# AudioHacker_v1_2.net
KiCad netlist of a schematic drawn in EAGLE
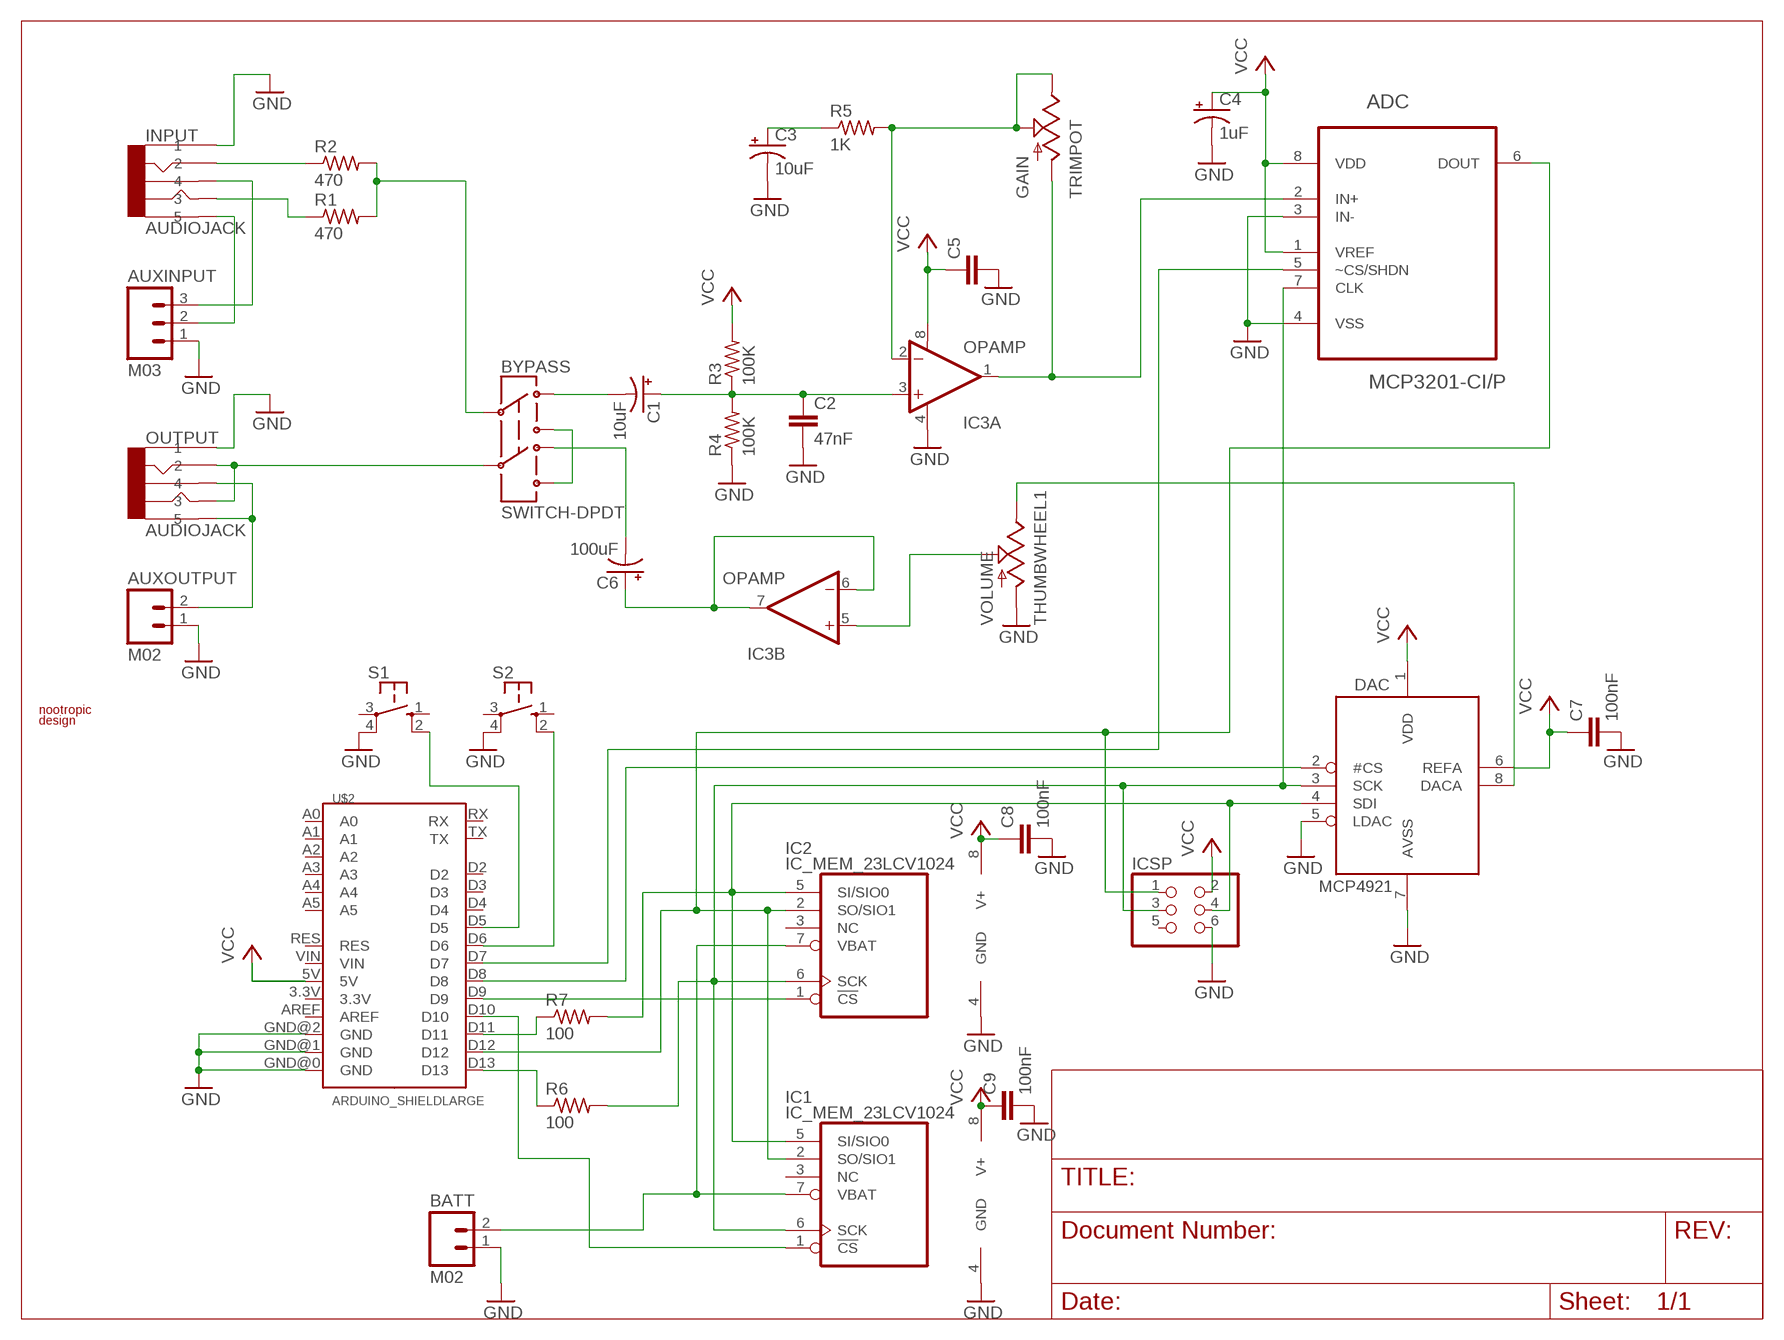
[diagram p0: schematic, sheet 1]

(export (version "E")
  (design (tool "Eeschema 10.0.6"))
  (components
    (comp (ref "ADC")
      (value "MCP3201-CI/P")
      (footprint "eagle-import:DIL08")
      (libsource (lib "eagle-import") (part "MCP3201-CI/P"))
    )
    (comp (ref "AUXINPUT")
      (value "M03")
      (footprint "eagle-import:1X03")
      (libsource (lib "eagle-import") (part "M03"))
    )
    (comp (ref "AUXOUTPUT")
      (value "M02")
      (footprint "eagle-import:1X02")
      (libsource (lib "eagle-import") (part "M02"))
    )
    (comp (ref "BATT")
      (value "M02")
      (footprint "eagle-import:1X02")
      (libsource (lib "eagle-import") (part "M02"))
    )
    (comp (ref "BYPASS")
      (value "SWITCH-DPDT")
      (footprint "eagle-import:OS")
      (libsource (lib "eagle-import") (part "SWITCH-DPDT"))
    )
    (comp (ref "C1")
      (value "10uF")
      (footprint "eagle-import:E2.5-5")
      (libsource (lib "eagle-import") (part "CAP-POL5MM"))
    )
    (comp (ref "C2")
      (value "47nF")
      (footprint "eagle-import:CAP-CERAMIC")
      (libsource (lib "eagle-import") (part "CAP"))
    )
    (comp (ref "C3")
      (value "10uF")
      (footprint "eagle-import:E2.5-5")
      (libsource (lib "eagle-import") (part "CAP-POL5MM"))
    )
    (comp (ref "C4")
      (value "1uF")
      (footprint "eagle-import:E2.5-5")
      (libsource (lib "eagle-import") (part "CAP-POL5MM"))
    )
    (comp (ref "C5")
      (value "CAPSMALL")
      (footprint "eagle-import:CAP-CERAMIC-SMALL")
      (libsource (lib "eagle-import") (part "CAPSMALL"))
    )
    (comp (ref "C6")
      (value "100uF")
      (footprint "eagle-import:E2.5-6")
      (libsource (lib "eagle-import") (part "CAP-POL6MM"))
    )
    (comp (ref "C7")
      (value "100nF")
      (footprint "eagle-import:CAP-CERAMIC-SMALL")
      (libsource (lib "eagle-import") (part "CAPSMALL"))
    )
    (comp (ref "C8")
      (value "100nF")
      (footprint "eagle-import:CAP-CERAMIC-SMALL")
      (libsource (lib "eagle-import") (part "CAPSMALL"))
    )
    (comp (ref "C9")
      (value "100nF")
      (footprint "eagle-import:CAP-CERAMIC-SMALL")
      (libsource (lib "eagle-import") (part "CAPSMALL"))
    )
    (comp (ref "DAC")
      (value "MCP4921")
      (footprint "eagle-import:DIL08")
      (libsource (lib "eagle-import") (part "MCP4921"))
    )
    (comp (ref "GAIN")
      (value "TRIMPOT")
      (footprint "eagle-import:TRIM_POT")
      (libsource (lib "eagle-import") (part "TRIMPOT"))
    )
    (comp (ref "IC1")
      (value "IC_MEM_23LCV1024")
      (footprint "eagle-import:DIL08")
      (libsource (lib "eagle-import") (part "IC_MEM_23LCV1024"))
    )
    (comp (ref "IC2")
      (value "IC_MEM_23LCV1024")
      (footprint "eagle-import:DIL08")
      (libsource (lib "eagle-import") (part "IC_MEM_23LCV1024"))
    )
    (comp (ref "IC3")
      (value "OPAMP")
      (footprint "eagle-import:DIL08")
      (libsource (lib "eagle-import") (part "OPAMP-DUAL"))
    )
    (comp (ref "ICSP")
      (value "PINHD-2X3")
      (footprint "eagle-import:2X03")
      (libsource (lib "eagle-import") (part "PINHD-2X3"))
    )
    (comp (ref "INPUT")
      (value "AUDIOJACK")
      (footprint "eagle-import:AUDIOJACK")
      (libsource (lib "eagle-import") (part "AUDIOJACK"))
    )
    (comp (ref "OUTPUT")
      (value "AUDIOJACK")
      (footprint "eagle-import:AUDIOJACK")
      (libsource (lib "eagle-import") (part "AUDIOJACK"))
    )
    (comp (ref "R1")
      (value "470")
      (footprint "eagle-import:0207_10")
      (libsource (lib "eagle-import") (part "R-US"))
    )
    (comp (ref "R2")
      (value "470")
      (footprint "eagle-import:0207_10")
      (libsource (lib "eagle-import") (part "R-US"))
    )
    (comp (ref "R3")
      (value "100K")
      (footprint "eagle-import:0207_10")
      (libsource (lib "eagle-import") (part "R-US"))
    )
    (comp (ref "R4")
      (value "100K")
      (footprint "eagle-import:0207_10")
      (libsource (lib "eagle-import") (part "R-US"))
    )
    (comp (ref "R5")
      (value "1K")
      (footprint "eagle-import:0207_10")
      (libsource (lib "eagle-import") (part "R-US"))
    )
    (comp (ref "R6")
      (value "100")
      (footprint "eagle-import:0207_10")
      (libsource (lib "eagle-import") (part "R-US"))
    )
    (comp (ref "R7")
      (value "100")
      (footprint "eagle-import:0207_10")
      (libsource (lib "eagle-import") (part "R-US"))
    )
    (comp (ref "S1")
      (value "SWITCH-TACTSWITCH-TACT-B")
      (footprint "eagle-import:SWITCH-TACT-B")
      (libsource (lib "eagle-import") (part "SWITCH-TACTSWITCH-TACT-B"))
    )
    (comp (ref "S2")
      (value "SWITCH-TACTSWITCH-TACT-B")
      (footprint "eagle-import:SWITCH-TACT-B")
      (libsource (lib "eagle-import") (part "SWITCH-TACTSWITCH-TACT-B"))
    )
    (comp (ref "U$2")
      (value "ARDUINO_SHIELDLARGE")
      (footprint "eagle-import:DUEMILANOVE_SHIELD_LARGE")
      (libsource (lib "eagle-import") (part "ARDUINO_SHIELDLARGE"))
    )
    (comp (ref "U$3")
      (value "LOGO")
      (footprint "eagle-import:LOGO_SMALL")
      (libsource (lib "eagle-import") (part "LOGO"))
    )
    (comp (ref "VOLUME")
      (value "THUMBWHEEL1")
      (footprint "eagle-import:THUMBWHEEL1")
      (libsource (lib "eagle-import") (part "THUMBWHEEL1"))
    )
  )
  (nets
    (net (code "1") (name "GND") (class "Default")
      (node (ref "ADC") (pin "3") (pinfunction "IN-_3") (pintype "input"))
      (node (ref "ADC") (pin "4") (pinfunction "VSS_4") (pintype "passive"))
      (node (ref "AUXINPUT") (pin "1") (pinfunction "2_1") (pintype "passive"))
      (node (ref "AUXOUTPUT") (pin "1") (pinfunction "1_1") (pintype "passive"))
      (node (ref "BATT") (pin "1") (pinfunction "1_1") (pintype "passive"))
      (node (ref "C2") (pin "2") (pinfunction "2_2") (pintype "passive"))
      (node (ref "C3") (pin "-") (pinfunction "-_-") (pintype "passive"))
      (node (ref "C4") (pin "-") (pinfunction "-_-") (pintype "passive"))
      (node (ref "C5") (pin "2") (pinfunction "2_2") (pintype "passive"))
      (node (ref "C7") (pin "2") (pinfunction "2_2") (pintype "passive"))
      (node (ref "C8") (pin "2") (pinfunction "2_2") (pintype "passive"))
      (node (ref "C9") (pin "2") (pinfunction "2_2") (pintype "passive"))
      (node (ref "DAC") (pin "5") (pinfunction "LDAC_5") (pintype "input"))
      (node (ref "DAC") (pin "7") (pinfunction "AVSS_7") (pintype "power_in"))
      (node (ref "IC1") (pin "4") (pinfunction "GND_4") (pintype "power_in"))
      (node (ref "IC2") (pin "4") (pinfunction "GND_4") (pintype "power_in"))
      (node (ref "IC3") (pin "4") (pinfunction "V-_4") (pintype "power_in"))
      (node (ref "ICSP") (pin "6") (pinfunction "6_6") (pintype "passive"))
      (node (ref "INPUT") (pin "1") (pinfunction "1_1") (pintype "bidirectional"))
      (node (ref "OUTPUT") (pin "1") (pinfunction "1_1") (pintype "bidirectional"))
      (node (ref "R4") (pin "1") (pinfunction "1_1") (pintype "passive"))
      (node (ref "S1") (pin "4") (pinfunction "P1_4") (pintype "passive"))
      (node (ref "S2") (pin "4") (pinfunction "P1_4") (pintype "passive"))
      (node (ref "U$2") (pin "GND@0") (pinfunction "GND_GND@0") (pintype "bidirectional"))
      (node (ref "U$2") (pin "GND@1") (pinfunction "GND_GND@1") (pintype "bidirectional"))
      (node (ref "U$2") (pin "GND@2") (pinfunction "GND_GND@2") (pintype "bidirectional"))
      (node (ref "VOLUME") (pin "P$1") (pinfunction "1_P$1") (pintype "passive"))
    )
    (net (code "2") (name "Net-(ADC-CLK)") (class "Default")
      (node (ref "ADC") (pin "7") (pinfunction "CLK_7") (pintype "input"))
      (node (ref "DAC") (pin "3") (pinfunction "SCK_3") (pintype "input"))
      (node (ref "IC1") (pin "6") (pinfunction "SCK_6") (pintype "input"))
      (node (ref "IC2") (pin "6") (pinfunction "SCK_6") (pintype "input"))
      (node (ref "ICSP") (pin "3") (pinfunction "3_3") (pintype "passive"))
      (node (ref "R6") (pin "2") (pinfunction "2_2") (pintype "passive"))
    )
    (net (code "3") (name "Net-(ADC-DOUT)") (class "Default")
      (node (ref "ADC") (pin "6") (pinfunction "DOUT_6") (pintype "output"))
      (node (ref "IC1") (pin "2") (pinfunction "SO/SIO1_2") (pintype "bidirectional"))
      (node (ref "IC2") (pin "2") (pinfunction "SO/SIO1_2") (pintype "bidirectional"))
      (node (ref "ICSP") (pin "1") (pinfunction "1_1") (pintype "passive"))
      (node (ref "U$2") (pin "D12") (pinfunction "D12_D12") (pintype "bidirectional"))
    )
    (net (code "4") (name "Net-(ADC-IN+)") (class "Default")
      (node (ref "ADC") (pin "2") (pinfunction "IN+_2") (pintype "input"))
      (node (ref "GAIN") (pin "1") (pinfunction "1_1") (pintype "passive"))
      (node (ref "IC3") (pin "1") (pinfunction "OUT_1") (pintype "output"))
    )
    (net (code "5") (name "Net-(ADC-~{CS{slash}SHDN})") (class "Default")
      (node (ref "ADC") (pin "5") (pinfunction "~{CS/SHDN}_5") (pintype "input"))
      (node (ref "U$2") (pin "D7") (pinfunction "D7_D7") (pintype "bidirectional"))
    )
    (net (code "6") (name "Net-(AUXINPUT-3)") (class "Default")
      (node (ref "AUXINPUT") (pin "2") (pinfunction "3_2") (pintype "passive"))
      (node (ref "INPUT") (pin "5") (pinfunction "5_5") (pintype "bidirectional"))
    )
    (net (code "7") (name "Net-(AUXINPUT-4)") (class "Default")
      (node (ref "AUXINPUT") (pin "3") (pinfunction "4_3") (pintype "passive"))
      (node (ref "INPUT") (pin "4") (pinfunction "4_4") (pintype "bidirectional"))
    )
    (net (code "8") (name "Net-(AUXOUTPUT-Pad2)") (class "Default")
      (node (ref "AUXOUTPUT") (pin "2") (pinfunction "2_2") (pintype "passive"))
      (node (ref "OUTPUT") (pin "4") (pinfunction "4_4") (pintype "bidirectional"))
      (node (ref "OUTPUT") (pin "5") (pinfunction "5_5") (pintype "bidirectional"))
    )
    (net (code "9") (name "Net-(BYPASS-Pad1)") (class "Default")
      (node (ref "BYPASS") (pin "1") (pinfunction "1_1") (pintype "bidirectional"))
      (node (ref "C1") (pin "-") (pinfunction "-_-") (pintype "passive"))
    )
    (net (code "10") (name "Net-(BYPASS-Pad2)") (class "Default")
      (node (ref "BYPASS") (pin "2") (pinfunction "2_2") (pintype "bidirectional"))
      (node (ref "R1") (pin "2") (pinfunction "2_2") (pintype "passive"))
      (node (ref "R2") (pin "2") (pinfunction "2_2") (pintype "passive"))
    )
    (net (code "11") (name "Net-(BYPASS-Pad3)") (class "Default")
      (node (ref "BYPASS") (pin "3") (pinfunction "3_3") (pintype "bidirectional"))
      (node (ref "BYPASS") (pin "6") (pinfunction "6_6") (pintype "bidirectional"))
    )
    (net (code "12") (name "Net-(BYPASS-Pad4)") (class "Default")
      (node (ref "BYPASS") (pin "4") (pinfunction "4_4") (pintype "bidirectional"))
      (node (ref "C6") (pin "-") (pinfunction "-_-") (pintype "passive"))
    )
    (net (code "13") (name "Net-(BYPASS-Pad5)") (class "Default")
      (node (ref "BYPASS") (pin "5") (pinfunction "5_5") (pintype "bidirectional"))
      (node (ref "OUTPUT") (pin "2") (pinfunction "2_2") (pintype "bidirectional"))
      (node (ref "OUTPUT") (pin "3") (pinfunction "3_3") (pintype "bidirectional"))
    )
    (net (code "14") (name "Net-(C3-Pad+)") (class "Default")
      (node (ref "C3") (pin "+") (pinfunction "+_+") (pintype "passive"))
      (node (ref "R5") (pin "1") (pinfunction "1_1") (pintype "passive"))
    )
    (net (code "15") (name "Net-(DAC-#CS)") (class "Default")
      (node (ref "DAC") (pin "2") (pinfunction "#CS_2") (pintype "input"))
      (node (ref "U$2") (pin "D8") (pinfunction "D8_D8") (pintype "bidirectional"))
    )
    (net (code "16") (name "Net-(DAC-DACA)") (class "Default")
      (node (ref "DAC") (pin "8") (pinfunction "DACA_8") (pintype "output"))
      (node (ref "VOLUME") (pin "P$3") (pinfunction "3_P$3") (pintype "passive"))
    )
    (net (code "17") (name "Net-(DAC-SDI)") (class "Default")
      (node (ref "DAC") (pin "4") (pinfunction "SDI_4") (pintype "input"))
      (node (ref "IC1") (pin "5") (pinfunction "SI/SIO0_5") (pintype "bidirectional"))
      (node (ref "IC2") (pin "5") (pinfunction "SI/SIO0_5") (pintype "bidirectional"))
      (node (ref "ICSP") (pin "4") (pinfunction "4_4") (pintype "passive"))
      (node (ref "R7") (pin "2") (pinfunction "2_2") (pintype "passive"))
    )
    (net (code "18") (name "Net-(IC1A-VBAT)") (class "Default")
      (node (ref "BATT") (pin "2") (pinfunction "2_2") (pintype "passive"))
      (node (ref "IC1") (pin "7") (pinfunction "VBAT_7") (pintype "passive"))
      (node (ref "IC2") (pin "7") (pinfunction "VBAT_7") (pintype "passive"))
    )
    (net (code "19") (name "Net-(IC1A-~{CS})") (class "Default")
      (node (ref "IC1") (pin "1") (pinfunction "~{CS}_1") (pintype "input"))
      (node (ref "U$2") (pin "D10") (pinfunction "D10_D10") (pintype "bidirectional"))
    )
    (net (code "20") (name "Net-(IC2A-~{CS})") (class "Default")
      (node (ref "IC2") (pin "1") (pinfunction "~{CS}_1") (pintype "input"))
      (node (ref "U$2") (pin "D9") (pinfunction "D9_D9") (pintype "bidirectional"))
    )
    (net (code "21") (name "Net-(IC3A-+IN)") (class "Default")
      (node (ref "C1") (pin "+") (pinfunction "+_+") (pintype "passive"))
      (node (ref "C2") (pin "1") (pinfunction "1_1") (pintype "passive"))
      (node (ref "IC3") (pin "3") (pinfunction "+IN_3") (pintype "input"))
      (node (ref "R3") (pin "1") (pinfunction "1_1") (pintype "passive"))
      (node (ref "R4") (pin "2") (pinfunction "2_2") (pintype "passive"))
    )
    (net (code "22") (name "Net-(IC3A--IN)") (class "Default")
      (node (ref "GAIN") (pin "2") (pinfunction "2_2") (pintype "passive"))
      (node (ref "GAIN") (pin "3") (pinfunction "3_3") (pintype "passive"))
      (node (ref "IC3") (pin "2") (pinfunction "-IN_2") (pintype "input"))
      (node (ref "R5") (pin "2") (pinfunction "2_2") (pintype "passive"))
    )
    (net (code "23") (name "Net-(IC3B-+IN)") (class "Default")
      (node (ref "IC3") (pin "5") (pinfunction "+IN_5") (pintype "input"))
      (node (ref "VOLUME") (pin "P$2") (pinfunction "2_P$2") (pintype "passive"))
    )
    (net (code "24") (name "Net-(IC3B--IN)") (class "Default")
      (node (ref "C6") (pin "+") (pinfunction "+_+") (pintype "passive"))
      (node (ref "IC3") (pin "6") (pinfunction "-IN_6") (pintype "input"))
      (node (ref "IC3") (pin "7") (pinfunction "OUT_7") (pintype "output"))
    )
    (net (code "25") (name "Net-(INPUT-Pad2)") (class "Default")
      (node (ref "INPUT") (pin "2") (pinfunction "2_2") (pintype "bidirectional"))
      (node (ref "R2") (pin "1") (pinfunction "1_1") (pintype "passive"))
    )
    (net (code "26") (name "Net-(INPUT-Pad3)") (class "Default")
      (node (ref "INPUT") (pin "3") (pinfunction "3_3") (pintype "bidirectional"))
      (node (ref "R1") (pin "1") (pinfunction "1_1") (pintype "passive"))
    )
    (net (code "27") (name "Net-(R6-Pad1)") (class "Default")
      (node (ref "R6") (pin "1") (pinfunction "1_1") (pintype "passive"))
      (node (ref "U$2") (pin "D13") (pinfunction "D13_D13") (pintype "bidirectional"))
    )
    (net (code "28") (name "Net-(R7-Pad1)") (class "Default")
      (node (ref "R7") (pin "1") (pinfunction "1_1") (pintype "passive"))
      (node (ref "U$2") (pin "D11") (pinfunction "D11_D11") (pintype "bidirectional"))
    )
    (net (code "29") (name "Net-(S1-S1)") (class "Default")
      (node (ref "S1") (pin "2") (pinfunction "S1_2") (pintype "passive"))
      (node (ref "U$2") (pin "D5") (pinfunction "D5_D5") (pintype "bidirectional"))
    )
    (net (code "30") (name "Net-(S2-S1)") (class "Default")
      (node (ref "S2") (pin "2") (pinfunction "S1_2") (pintype "passive"))
      (node (ref "U$2") (pin "D6") (pinfunction "D6_D6") (pintype "bidirectional"))
    )
    (net (code "31") (name "VCC") (class "Default")
      (node (ref "ADC") (pin "1") (pinfunction "VREF_1") (pintype "input"))
      (node (ref "ADC") (pin "8") (pinfunction "VDD_8") (pintype "power_in"))
      (node (ref "C4") (pin "+") (pinfunction "+_+") (pintype "passive"))
      (node (ref "C5") (pin "1") (pinfunction "1_1") (pintype "passive"))
      (node (ref "C7") (pin "1") (pinfunction "1_1") (pintype "passive"))
      (node (ref "C8") (pin "1") (pinfunction "1_1") (pintype "passive"))
      (node (ref "C9") (pin "1") (pinfunction "1_1") (pintype "passive"))
      (node (ref "DAC") (pin "1") (pinfunction "VDD_1") (pintype "power_in"))
      (node (ref "DAC") (pin "6") (pinfunction "REFA_6") (pintype "input"))
      (node (ref "IC1") (pin "8") (pinfunction "V+_8") (pintype "power_in"))
      (node (ref "IC2") (pin "8") (pinfunction "V+_8") (pintype "power_in"))
      (node (ref "IC3") (pin "8") (pinfunction "V+_8") (pintype "power_in"))
      (node (ref "ICSP") (pin "2") (pinfunction "2_2") (pintype "passive"))
      (node (ref "R3") (pin "2") (pinfunction "2_2") (pintype "passive"))
      (node (ref "U$2") (pin "5V") (pinfunction "5V_5V") (pintype "bidirectional"))
    )
    (net (code "32") (name "unconnected-(IC1A-NC-Pad3)") (class "Default")
      (node (ref "IC1") (pin "3") (pinfunction "NC_3") (pintype "bidirectional"))
    )
    (net (code "33") (name "unconnected-(IC2A-NC-Pad3)") (class "Default")
      (node (ref "IC2") (pin "3") (pinfunction "NC_3") (pintype "bidirectional"))
    )
    (net (code "34") (name "unconnected-(ICSP-Pad5)") (class "Default")
      (node (ref "ICSP") (pin "5") (pinfunction "5_5") (pintype "passive"))
    )
    (net (code "35") (name "unconnected-(S1-P-Pad3)") (class "Default")
      (node (ref "S1") (pin "3") (pinfunction "P_3") (pintype "passive"))
    )
    (net (code "36") (name "unconnected-(S1-S-Pad1)") (class "Default")
      (node (ref "S1") (pin "1") (pinfunction "S_1") (pintype "passive"))
    )
    (net (code "37") (name "unconnected-(S2-P-Pad3)") (class "Default")
      (node (ref "S2") (pin "3") (pinfunction "P_3") (pintype "passive"))
    )
    (net (code "38") (name "unconnected-(S2-S-Pad1)") (class "Default")
      (node (ref "S2") (pin "1") (pinfunction "S_1") (pintype "passive"))
    )
    (net (code "39") (name "unconnected-(U$2-Pad3.3V)") (class "Default")
      (node (ref "U$2") (pin "3.3V") (pinfunction "3.3V_3.3V") (pintype "bidirectional"))
    )
    (net (code "40") (name "unconnected-(U$2-PadA0)") (class "Default")
      (node (ref "U$2") (pin "A0") (pinfunction "A0_A0") (pintype "bidirectional"))
    )
    (net (code "41") (name "unconnected-(U$2-PadA1)") (class "Default")
      (node (ref "U$2") (pin "A1") (pinfunction "A1_A1") (pintype "bidirectional"))
    )
    (net (code "42") (name "unconnected-(U$2-PadA2)") (class "Default")
      (node (ref "U$2") (pin "A2") (pinfunction "A2_A2") (pintype "bidirectional"))
    )
    (net (code "43") (name "unconnected-(U$2-PadA3)") (class "Default")
      (node (ref "U$2") (pin "A3") (pinfunction "A3_A3") (pintype "bidirectional"))
    )
    (net (code "44") (name "unconnected-(U$2-PadA4)") (class "Default")
      (node (ref "U$2") (pin "A4") (pinfunction "A4_A4") (pintype "bidirectional"))
    )
    (net (code "45") (name "unconnected-(U$2-PadA5)") (class "Default")
      (node (ref "U$2") (pin "A5") (pinfunction "A5_A5") (pintype "bidirectional"))
    )
    (net (code "46") (name "unconnected-(U$2-PadAREF)") (class "Default")
      (node (ref "U$2") (pin "AREF") (pinfunction "AREF_AREF") (pintype "bidirectional"))
    )
    (net (code "47") (name "unconnected-(U$2-PadD2)") (class "Default")
      (node (ref "U$2") (pin "D2") (pinfunction "D2_D2") (pintype "bidirectional"))
    )
    (net (code "48") (name "unconnected-(U$2-PadD3)") (class "Default")
      (node (ref "U$2") (pin "D3") (pinfunction "D3_D3") (pintype "bidirectional"))
    )
    (net (code "49") (name "unconnected-(U$2-PadD4)") (class "Default")
      (node (ref "U$2") (pin "D4") (pinfunction "D4_D4") (pintype "bidirectional"))
    )
    (net (code "50") (name "unconnected-(U$2-PadRES)") (class "Default")
      (node (ref "U$2") (pin "RES") (pinfunction "RES_RES") (pintype "bidirectional"))
    )
    (net (code "51") (name "unconnected-(U$2-PadRX)") (class "Default")
      (node (ref "U$2") (pin "RX") (pinfunction "RX_RX") (pintype "bidirectional"))
    )
    (net (code "52") (name "unconnected-(U$2-PadTX)") (class "Default")
      (node (ref "U$2") (pin "TX") (pinfunction "TX_TX") (pintype "bidirectional"))
    )
    (net (code "53") (name "unconnected-(U$2-PadVIN)") (class "Default")
      (node (ref "U$2") (pin "VIN") (pinfunction "VIN_VIN") (pintype "bidirectional"))
    )
  )
)
